# dualevse.net
KiCad netlist of a schematic drawn in EAGLE
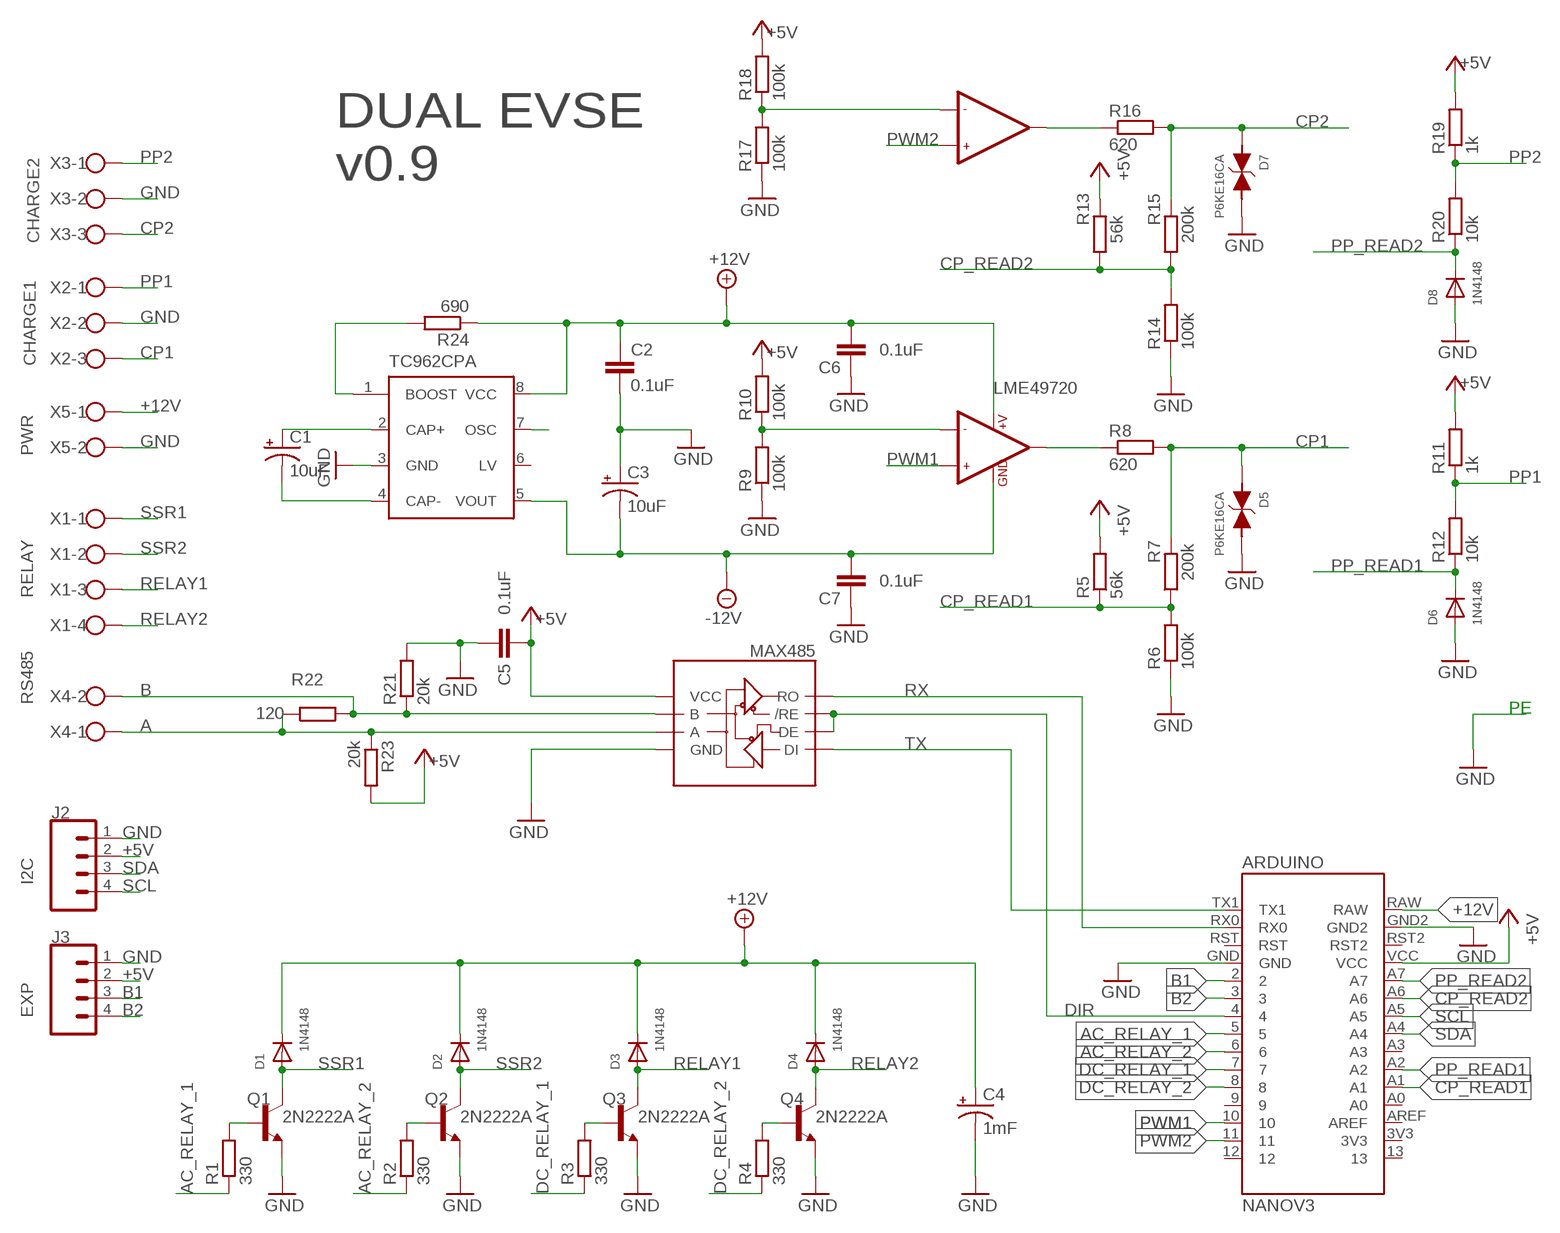
[diagram p0: schematic, sheet 1]

(export (version "E")
  (design (tool "Eeschema 10.0.6"))
  (components
    (comp (ref "ARDUINO")
      (value "NANOV3")
      (footprint "eagle-import:NANOV3")
      (libsource (lib "eagle-import") (part "NANOV3"))
    )
    (comp (ref "C1")
      (value "10uF")
      (footprint "eagle-import:CPOL-RADIAL-2.5MM-5MM")
      (libsource (lib "eagle-import") (part "10UF-POLAR-RADIAL-2.5MM-25V-20%"))
    )
    (comp (ref "C2")
      (value "0.1uF")
      (footprint "eagle-import:CAP-PTH-SMALL-KIT")
      (libsource (lib "eagle-import") (part "0.1UF-KIT-EZ-50V-20%"))
    )
    (comp (ref "C3")
      (value "10uF")
      (footprint "eagle-import:CPOL-RADIAL-2.5MM-5MM")
      (libsource (lib "eagle-import") (part "10UF-POLAR-RADIAL-2.5MM-25V-20%"))
    )
    (comp (ref "C4")
      (value "1mF")
      (footprint "eagle-import:CPOL-RADIAL-5MM-10MM")
      (libsource (lib "eagle-import") (part "1000UF-RADIAL-5MM-25V-20%"))
    )
    (comp (ref "C5")
      (value "0.1uF")
      (footprint "eagle-import:CAP-PTH-SMALL-KIT")
      (libsource (lib "eagle-import") (part "0.1UF-KIT-EZ-50V-20%"))
    )
    (comp (ref "C6")
      (value "0.1uF")
      (footprint "eagle-import:CAP-PTH-SMALL-KIT")
      (libsource (lib "eagle-import") (part "0.1UF-KIT-EZ-50V-20%"))
    )
    (comp (ref "C7")
      (value "0.1uF")
      (footprint "eagle-import:CAP-PTH-SMALL-KIT")
      (libsource (lib "eagle-import") (part "0.1UF-KIT-EZ-50V-20%"))
    )
    (comp (ref "D1")
      (value "1N4148")
      (footprint "eagle-import:DO-1N4148")
      (libsource (lib "eagle-import") (part "DIODEDO-1N4148"))
    )
    (comp (ref "D2")
      (value "1N4148")
      (footprint "eagle-import:DO-1N4148")
      (libsource (lib "eagle-import") (part "DIODEDO-1N4148"))
    )
    (comp (ref "D3")
      (value "1N4148")
      (footprint "eagle-import:DO-1N4148")
      (libsource (lib "eagle-import") (part "DIODEDO-1N4148"))
    )
    (comp (ref "D4")
      (value "1N4148")
      (footprint "eagle-import:DO-1N4148")
      (libsource (lib "eagle-import") (part "DIODEDO-1N4148"))
    )
    (comp (ref "D5")
      (value "P6KE16CA")
      (footprint "eagle-import:C4111-15")
      (libsource (lib "eagle-import") (part "TVSDO2"))
    )
    (comp (ref "D6")
      (value "1N4148")
      (footprint "eagle-import:DO-1N4148")
      (libsource (lib "eagle-import") (part "DIODEDO-1N4148"))
    )
    (comp (ref "D7")
      (value "P6KE16CA")
      (footprint "eagle-import:C4111-15")
      (libsource (lib "eagle-import") (part "TVSDO2"))
    )
    (comp (ref "D8")
      (value "1N4148")
      (footprint "eagle-import:DO-1N4148")
      (libsource (lib "eagle-import") (part "DIODEDO-1N4148"))
    )
    (comp (ref "J2")
      (value "I2C")
      (footprint "eagle-import:MOLEX-1X4")
      (libsource (lib "eagle-import") (part "CONN_04POLAR"))
    )
    (comp (ref "J3")
      (value "EXP")
      (footprint "eagle-import:MOLEX-1X4")
      (libsource (lib "eagle-import") (part "CONN_04POLAR"))
    )
    (comp (ref "LME49720")
      (value "LME49720")
      (footprint "eagle-import:TEXAS_DIL08")
      (libsource (lib "eagle-import") (part "LF353DIL08"))
    )
    (comp (ref "MAX485")
      (value "SPARKFUN-IC-COMMS_RS485")
      (footprint "eagle-import:TEXAS_DIL08")
      (libsource (lib "eagle-import") (part "SPARKFUN-IC-COMMS_RS485"))
    )
    (comp (ref "Q1")
      (value "2N2222A")
      (footprint "eagle-import:TO18")
      (libsource (lib "eagle-import") (part "2N2222A"))
    )
    (comp (ref "Q2")
      (value "2N2222A")
      (footprint "eagle-import:TO18")
      (libsource (lib "eagle-import") (part "2N2222A"))
    )
    (comp (ref "Q3")
      (value "2N2222A")
      (footprint "eagle-import:TO18")
      (libsource (lib "eagle-import") (part "2N2222A"))
    )
    (comp (ref "Q4")
      (value "2N2222A")
      (footprint "eagle-import:TO18")
      (libsource (lib "eagle-import") (part "2N2222A"))
    )
    (comp (ref "R1")
      (value "330")
      (footprint "eagle-import:0207_10")
      (libsource (lib "eagle-import") (part "R-EU_0207/10"))
    )
    (comp (ref "R2")
      (value "330")
      (footprint "eagle-import:0207_10")
      (libsource (lib "eagle-import") (part "R-EU_0207/10"))
    )
    (comp (ref "R3")
      (value "330")
      (footprint "eagle-import:0207_10")
      (libsource (lib "eagle-import") (part "R-EU_0207/10"))
    )
    (comp (ref "R4")
      (value "330")
      (footprint "eagle-import:0207_10")
      (libsource (lib "eagle-import") (part "R-EU_0207/10"))
    )
    (comp (ref "R5")
      (value "56k")
      (footprint "eagle-import:0207_10")
      (libsource (lib "eagle-import") (part "R-EU_0207/10"))
    )
    (comp (ref "R6")
      (value "100k")
      (footprint "eagle-import:0207_10")
      (libsource (lib "eagle-import") (part "R-EU_0207/10"))
    )
    (comp (ref "R7")
      (value "200k")
      (footprint "eagle-import:0207_10")
      (libsource (lib "eagle-import") (part "R-EU_0207/10"))
    )
    (comp (ref "R8")
      (value "620")
      (footprint "eagle-import:0207_10")
      (libsource (lib "eagle-import") (part "R-EU_0207/10"))
    )
    (comp (ref "R9")
      (value "100k")
      (footprint "eagle-import:0207_10")
      (libsource (lib "eagle-import") (part "R-EU_0207/10"))
    )
    (comp (ref "R10")
      (value "100k")
      (footprint "eagle-import:0207_10")
      (libsource (lib "eagle-import") (part "R-EU_0207/10"))
    )
    (comp (ref "R11")
      (value "1k")
      (footprint "eagle-import:0207_10")
      (libsource (lib "eagle-import") (part "R-EU_0207/10"))
    )
    (comp (ref "R12")
      (value "10k")
      (footprint "eagle-import:0207_10")
      (libsource (lib "eagle-import") (part "R-EU_0207/10"))
    )
    (comp (ref "R13")
      (value "56k")
      (footprint "eagle-import:0207_10")
      (libsource (lib "eagle-import") (part "R-EU_0207/10"))
    )
    (comp (ref "R14")
      (value "100k")
      (footprint "eagle-import:0207_10")
      (libsource (lib "eagle-import") (part "R-EU_0207/10"))
    )
    (comp (ref "R15")
      (value "200k")
      (footprint "eagle-import:0207_10")
      (libsource (lib "eagle-import") (part "R-EU_0207/10"))
    )
    (comp (ref "R16")
      (value "620")
      (footprint "eagle-import:0207_10")
      (libsource (lib "eagle-import") (part "R-EU_0207/10"))
    )
    (comp (ref "R17")
      (value "100k")
      (footprint "eagle-import:0207_10")
      (libsource (lib "eagle-import") (part "R-EU_0207/10"))
    )
    (comp (ref "R18")
      (value "100k")
      (footprint "eagle-import:0207_10")
      (libsource (lib "eagle-import") (part "R-EU_0207/10"))
    )
    (comp (ref "R19")
      (value "1k")
      (footprint "eagle-import:0207_10")
      (libsource (lib "eagle-import") (part "R-EU_0207/10"))
    )
    (comp (ref "R20")
      (value "10k")
      (footprint "eagle-import:0207_10")
      (libsource (lib "eagle-import") (part "R-EU_0207/10"))
    )
    (comp (ref "R21")
      (value "20k")
      (footprint "eagle-import:0207_10")
      (libsource (lib "eagle-import") (part "R-EU_0207/10"))
    )
    (comp (ref "R22")
      (value "120")
      (footprint "eagle-import:0207_10")
      (libsource (lib "eagle-import") (part "R-EU_0207/10"))
    )
    (comp (ref "R23")
      (value "20k")
      (footprint "eagle-import:0207_10")
      (libsource (lib "eagle-import") (part "R-EU_0207/10"))
    )
    (comp (ref "R24")
      (value "690")
      (footprint "eagle-import:0207_10")
      (libsource (lib "eagle-import") (part "R-EU_0207/10"))
    )
    (comp (ref "TC962CPA")
      (value "TEXAS_TL7660")
      (footprint "eagle-import:TEXAS_DIL08")
      (libsource (lib "eagle-import") (part "TEXAS_TL7660"))
    )
    (comp (ref "X1")
      (value "RELAY")
      (footprint "eagle-import:W237-4")
      (libsource (lib "eagle-import") (part "W237-4"))
    )
    (comp (ref "X2")
      (value "CHARGE1")
      (footprint "eagle-import:W237-103")
      (fields (field (name "MPN") "237-103"))
      (libsource (lib "eagle-import") (part "W237-103"))
    )
    (comp (ref "X3")
      (value "CHARGE2")
      (footprint "eagle-import:W237-103")
      (fields (field (name "MPN") "237-103"))
      (libsource (lib "eagle-import") (part "W237-103"))
    )
    (comp (ref "X4")
      (value "RS485")
      (footprint "eagle-import:W237-102")
      (fields (field (name "MPN") "237-102"))
      (libsource (lib "eagle-import") (part "W237-102"))
    )
    (comp (ref "X5")
      (value "PWR")
      (footprint "eagle-import:W237-102")
      (fields (field (name "MPN") "237-102"))
      (libsource (lib "eagle-import") (part "W237-102"))
    )
  )
  (nets
    (net (code "1") (name "+5V") (class "Default")
      (node (ref "ARDUINO") (pin "VCC") (pinfunction "VCC_VCC") (pintype "bidirectional"))
      (node (ref "C5") (pin "2") (pinfunction "2_2") (pintype "passive"))
      (node (ref "J2") (pin "2") (pinfunction "2_2") (pintype "passive"))
      (node (ref "J3") (pin "2") (pinfunction "2_2") (pintype "passive"))
      (node (ref "MAX485") (pin "8") (pinfunction "VCC_8") (pintype "bidirectional"))
      (node (ref "R10") (pin "2") (pinfunction "2_2") (pintype "passive"))
      (node (ref "R11") (pin "2") (pinfunction "2_2") (pintype "passive"))
      (node (ref "R13") (pin "2") (pinfunction "2_2") (pintype "passive"))
      (node (ref "R18") (pin "2") (pinfunction "2_2") (pintype "passive"))
      (node (ref "R19") (pin "2") (pinfunction "2_2") (pintype "passive"))
      (node (ref "R23") (pin "2") (pinfunction "2_2") (pintype "passive"))
      (node (ref "R5") (pin "2") (pinfunction "2_2") (pintype "passive"))
    )
    (net (code "2") (name "+12V") (class "Default")
      (node (ref "ARDUINO") (pin "RAW") (pinfunction "RAW_RAW") (pintype "bidirectional"))
      (node (ref "C2") (pin "1") (pinfunction "1_1") (pintype "passive"))
      (node (ref "C4") (pin "+") (pinfunction "+_+") (pintype "passive"))
      (node (ref "C6") (pin "1") (pinfunction "1_1") (pintype "passive"))
      (node (ref "D1") (pin "C") (pinfunction "C_C") (pintype "passive"))
      (node (ref "D2") (pin "C") (pinfunction "C_C") (pintype "passive"))
      (node (ref "D3") (pin "C") (pinfunction "C_C") (pintype "passive"))
      (node (ref "D4") (pin "C") (pinfunction "C_C") (pintype "passive"))
      (node (ref "LME49720") (pin "8") (pinfunction "+V_8") (pintype "power_in"))
      (node (ref "R24") (pin "1") (pinfunction "1_1") (pintype "passive"))
      (node (ref "TC962CPA") (pin "8") (pinfunction "VCC_8") (pintype "power_in"))
      (node (ref "X5") (pin "1") (pinfunction "KL_1") (pintype "passive"))
    )
    (net (code "3") (name "-12V") (class "Default")
      (node (ref "C3") (pin "2") (pinfunction "-_2") (pintype "passive"))
      (node (ref "C7") (pin "2") (pinfunction "2_2") (pintype "passive"))
      (node (ref "LME49720") (pin "4") (pinfunction "GND_4") (pintype "power_in"))
      (node (ref "TC962CPA") (pin "5") (pinfunction "VOUT_5") (pintype "passive"))
    )
    (net (code "4") (name "/A") (class "Default")
      (node (ref "MAX485") (pin "6") (pinfunction "A_6") (pintype "bidirectional"))
      (node (ref "R22") (pin "1") (pinfunction "1_1") (pintype "passive"))
      (node (ref "R23") (pin "1") (pinfunction "1_1") (pintype "passive"))
      (node (ref "X4") (pin "1") (pinfunction "KL_1") (pintype "passive"))
    )
    (net (code "5") (name "/B") (class "Default")
      (node (ref "MAX485") (pin "7") (pinfunction "B_7") (pintype "bidirectional"))
      (node (ref "R21") (pin "1") (pinfunction "1_1") (pintype "passive"))
      (node (ref "R22") (pin "2") (pinfunction "2_2") (pintype "passive"))
      (node (ref "X4") (pin "2") (pinfunction "KL_2") (pintype "passive"))
    )
    (net (code "6") (name "/CP1") (class "Default")
      (node (ref "D5") (pin "A") (pinfunction "1_A") (pintype "passive"))
      (node (ref "R7") (pin "2") (pinfunction "2_2") (pintype "passive"))
      (node (ref "R8") (pin "2") (pinfunction "2_2") (pintype "passive"))
      (node (ref "X2") (pin "3") (pinfunction "KL_3") (pintype "passive"))
    )
    (net (code "7") (name "/CP2") (class "Default")
      (node (ref "D7") (pin "A") (pinfunction "1_A") (pintype "passive"))
      (node (ref "R15") (pin "2") (pinfunction "2_2") (pintype "passive"))
      (node (ref "R16") (pin "2") (pinfunction "2_2") (pintype "passive"))
      (node (ref "X3") (pin "3") (pinfunction "KL_3") (pintype "passive"))
    )
    (net (code "8") (name "/DIR") (class "Default")
      (node (ref "ARDUINO") (pin "4") (pinfunction "4_4") (pintype "bidirectional"))
      (node (ref "MAX485") (pin "2") (pinfunction "/RE_2") (pintype "bidirectional"))
      (node (ref "MAX485") (pin "3") (pinfunction "DE_3") (pintype "bidirectional"))
    )
    (net (code "9") (name "/PP1") (class "Default")
      (node (ref "R11") (pin "1") (pinfunction "1_1") (pintype "passive"))
      (node (ref "R12") (pin "2") (pinfunction "2_2") (pintype "passive"))
      (node (ref "X2") (pin "1") (pinfunction "KL_1") (pintype "passive"))
    )
    (net (code "10") (name "/PP2") (class "Default")
      (node (ref "R19") (pin "1") (pinfunction "1_1") (pintype "passive"))
      (node (ref "R20") (pin "2") (pinfunction "2_2") (pintype "passive"))
      (node (ref "X3") (pin "1") (pinfunction "KL_1") (pintype "passive"))
    )
    (net (code "11") (name "/RELAY1") (class "Default")
      (node (ref "D3") (pin "A") (pinfunction "A_A") (pintype "passive"))
      (node (ref "Q3") (pin "3") (pinfunction "C_3") (pintype "passive"))
      (node (ref "X1") (pin "3") (pinfunction "KL_3") (pintype "passive"))
    )
    (net (code "12") (name "/RELAY2") (class "Default")
      (node (ref "D4") (pin "A") (pinfunction "A_A") (pintype "passive"))
      (node (ref "Q4") (pin "3") (pinfunction "C_3") (pintype "passive"))
      (node (ref "X1") (pin "4") (pinfunction "KL_4") (pintype "passive"))
    )
    (net (code "13") (name "/RX") (class "Default")
      (node (ref "ARDUINO") (pin "RX0") (pinfunction "RX0_RX0") (pintype "bidirectional"))
      (node (ref "MAX485") (pin "1") (pinfunction "RO_1") (pintype "bidirectional"))
    )
    (net (code "14") (name "/SSR1") (class "Default")
      (node (ref "D1") (pin "A") (pinfunction "A_A") (pintype "passive"))
      (node (ref "Q1") (pin "3") (pinfunction "C_3") (pintype "passive"))
      (node (ref "X1") (pin "1") (pinfunction "KL_1") (pintype "passive"))
    )
    (net (code "15") (name "/SSR2") (class "Default")
      (node (ref "D2") (pin "A") (pinfunction "A_A") (pintype "passive"))
      (node (ref "Q2") (pin "3") (pinfunction "C_3") (pintype "passive"))
      (node (ref "X1") (pin "2") (pinfunction "KL_2") (pintype "passive"))
    )
    (net (code "16") (name "/TX") (class "Default")
      (node (ref "ARDUINO") (pin "TX1") (pinfunction "TX1_TX1") (pintype "bidirectional"))
      (node (ref "MAX485") (pin "4") (pinfunction "DI_4") (pintype "bidirectional"))
    )
    (net (code "17") (name "AC_RELAY_1") (class "Default")
      (node (ref "ARDUINO") (pin "5") (pinfunction "5_5") (pintype "bidirectional"))
      (node (ref "R1") (pin "1") (pinfunction "1_1") (pintype "passive"))
    )
    (net (code "18") (name "AC_RELAY_2") (class "Default")
      (node (ref "ARDUINO") (pin "6") (pinfunction "6_6") (pintype "bidirectional"))
      (node (ref "R2") (pin "1") (pinfunction "1_1") (pintype "passive"))
    )
    (net (code "19") (name "B1") (class "Default")
      (node (ref "ARDUINO") (pin "2") (pinfunction "2_2") (pintype "bidirectional"))
      (node (ref "J3") (pin "3") (pinfunction "3_3") (pintype "passive"))
    )
    (net (code "20") (name "B2") (class "Default")
      (node (ref "ARDUINO") (pin "3") (pinfunction "3_3") (pintype "bidirectional"))
      (node (ref "J3") (pin "4") (pinfunction "4_4") (pintype "passive"))
    )
    (net (code "21") (name "CP_READ1") (class "Default")
      (node (ref "ARDUINO") (pin "A1") (pinfunction "A1_A1") (pintype "bidirectional"))
      (node (ref "R5") (pin "1") (pinfunction "1_1") (pintype "passive"))
      (node (ref "R6") (pin "2") (pinfunction "2_2") (pintype "passive"))
      (node (ref "R7") (pin "1") (pinfunction "1_1") (pintype "passive"))
    )
    (net (code "22") (name "CP_READ2") (class "Default")
      (node (ref "ARDUINO") (pin "A6") (pinfunction "A6_A6") (pintype "bidirectional"))
      (node (ref "R13") (pin "1") (pinfunction "1_1") (pintype "passive"))
      (node (ref "R14") (pin "2") (pinfunction "2_2") (pintype "passive"))
      (node (ref "R15") (pin "1") (pinfunction "1_1") (pintype "passive"))
    )
    (net (code "23") (name "DC_RELAY_1") (class "Default")
      (node (ref "ARDUINO") (pin "7") (pinfunction "7_7") (pintype "bidirectional"))
      (node (ref "R3") (pin "1") (pinfunction "1_1") (pintype "passive"))
    )
    (net (code "24") (name "DC_RELAY_2") (class "Default")
      (node (ref "ARDUINO") (pin "8") (pinfunction "8_8") (pintype "bidirectional"))
      (node (ref "R4") (pin "1") (pinfunction "1_1") (pintype "passive"))
    )
    (net (code "25") (name "GND") (class "Default")
      (node (ref "ARDUINO") (pin "GND") (pinfunction "GND_GND") (pintype "bidirectional"))
      (node (ref "ARDUINO") (pin "GND2") (pinfunction "GND2_GND2") (pintype "bidirectional"))
      (node (ref "C2") (pin "2") (pinfunction "2_2") (pintype "passive"))
      (node (ref "C3") (pin "1") (pinfunction "+_1") (pintype "passive"))
      (node (ref "C4") (pin "-") (pinfunction "-_-") (pintype "passive"))
      (node (ref "C5") (pin "1") (pinfunction "1_1") (pintype "passive"))
      (node (ref "C6") (pin "2") (pinfunction "2_2") (pintype "passive"))
      (node (ref "C7") (pin "1") (pinfunction "1_1") (pintype "passive"))
      (node (ref "D5") (pin "C") (pinfunction "2_C") (pintype "passive"))
      (node (ref "D6") (pin "A") (pinfunction "A_A") (pintype "passive"))
      (node (ref "D7") (pin "C") (pinfunction "2_C") (pintype "passive"))
      (node (ref "D8") (pin "A") (pinfunction "A_A") (pintype "passive"))
      (node (ref "J2") (pin "1") (pinfunction "1_1") (pintype "passive"))
      (node (ref "J3") (pin "1") (pinfunction "1_1") (pintype "passive"))
      (node (ref "MAX485") (pin "5") (pinfunction "GND_5") (pintype "bidirectional"))
      (node (ref "Q1") (pin "1") (pinfunction "E_1") (pintype "passive"))
      (node (ref "Q2") (pin "1") (pinfunction "E_1") (pintype "passive"))
      (node (ref "Q3") (pin "1") (pinfunction "E_1") (pintype "passive"))
      (node (ref "Q4") (pin "1") (pinfunction "E_1") (pintype "passive"))
      (node (ref "R14") (pin "1") (pinfunction "1_1") (pintype "passive"))
      (node (ref "R17") (pin "1") (pinfunction "1_1") (pintype "passive"))
      (node (ref "R21") (pin "2") (pinfunction "2_2") (pintype "passive"))
      (node (ref "R6") (pin "1") (pinfunction "1_1") (pintype "passive"))
      (node (ref "R9") (pin "1") (pinfunction "1_1") (pintype "passive"))
      (node (ref "TC962CPA") (pin "3") (pinfunction "GND_3") (pintype "power_in"))
      (node (ref "X2") (pin "2") (pinfunction "KL_2") (pintype "passive"))
      (node (ref "X3") (pin "2") (pinfunction "KL_2") (pintype "passive"))
      (node (ref "X5") (pin "2") (pinfunction "KL_2") (pintype "passive"))
    )
    (net (code "26") (name "Net-(C1-+)") (class "Default")
      (node (ref "C1") (pin "1") (pinfunction "+_1") (pintype "passive"))
      (node (ref "TC962CPA") (pin "2") (pinfunction "CAP+_2") (pintype "passive"))
    )
    (net (code "27") (name "Net-(C1--)") (class "Default")
      (node (ref "C1") (pin "2") (pinfunction "-_2") (pintype "passive"))
      (node (ref "TC962CPA") (pin "4") (pinfunction "CAP-_4") (pintype "passive"))
    )
    (net (code "28") (name "Net-(LME49720A--IN1)") (class "Default")
      (node (ref "LME49720") (pin "2") (pinfunction "-IN1_2") (pintype "input"))
      (node (ref "R10") (pin "1") (pinfunction "1_1") (pintype "passive"))
      (node (ref "R9") (pin "2") (pinfunction "2_2") (pintype "passive"))
    )
    (net (code "29") (name "Net-(LME49720A-OUT1)") (class "Default")
      (node (ref "LME49720") (pin "1") (pinfunction "OUT1_1") (pintype "output"))
      (node (ref "R8") (pin "1") (pinfunction "1_1") (pintype "passive"))
    )
    (net (code "30") (name "Net-(LME49720B--IN2)") (class "Default")
      (node (ref "LME49720") (pin "6") (pinfunction "-IN2_6") (pintype "input"))
      (node (ref "R17") (pin "2") (pinfunction "2_2") (pintype "passive"))
      (node (ref "R18") (pin "1") (pinfunction "1_1") (pintype "passive"))
    )
    (net (code "31") (name "Net-(LME49720B-OUT2)") (class "Default")
      (node (ref "LME49720") (pin "7") (pinfunction "OUT2_7") (pintype "output"))
      (node (ref "R16") (pin "1") (pinfunction "1_1") (pintype "passive"))
    )
    (net (code "32") (name "Net-(Q1-B)") (class "Default")
      (node (ref "Q1") (pin "2") (pinfunction "B_2") (pintype "passive"))
      (node (ref "R1") (pin "2") (pinfunction "2_2") (pintype "passive"))
    )
    (net (code "33") (name "Net-(Q2-B)") (class "Default")
      (node (ref "Q2") (pin "2") (pinfunction "B_2") (pintype "passive"))
      (node (ref "R2") (pin "2") (pinfunction "2_2") (pintype "passive"))
    )
    (net (code "34") (name "Net-(Q3-B)") (class "Default")
      (node (ref "Q3") (pin "2") (pinfunction "B_2") (pintype "passive"))
      (node (ref "R3") (pin "2") (pinfunction "2_2") (pintype "passive"))
    )
    (net (code "35") (name "Net-(Q4-B)") (class "Default")
      (node (ref "Q4") (pin "2") (pinfunction "B_2") (pintype "passive"))
      (node (ref "R4") (pin "2") (pinfunction "2_2") (pintype "passive"))
    )
    (net (code "36") (name "Net-(TC962CPA-BOOST)") (class "Default")
      (node (ref "R24") (pin "2") (pinfunction "2_2") (pintype "passive"))
      (node (ref "TC962CPA") (pin "1") (pinfunction "BOOST_1") (pintype "bidirectional"))
    )
    (net (code "37") (name "PP_READ1") (class "Default")
      (node (ref "ARDUINO") (pin "A2") (pinfunction "A2_A2") (pintype "bidirectional"))
      (node (ref "D6") (pin "C") (pinfunction "C_C") (pintype "passive"))
      (node (ref "R12") (pin "1") (pinfunction "1_1") (pintype "passive"))
    )
    (net (code "38") (name "PP_READ2") (class "Default")
      (node (ref "ARDUINO") (pin "A7") (pinfunction "A7_A7") (pintype "bidirectional"))
      (node (ref "D8") (pin "C") (pinfunction "C_C") (pintype "passive"))
      (node (ref "R20") (pin "1") (pinfunction "1_1") (pintype "passive"))
    )
    (net (code "39") (name "PWM1") (class "Default")
      (node (ref "ARDUINO") (pin "10") (pinfunction "10_10") (pintype "bidirectional"))
      (node (ref "LME49720") (pin "3") (pinfunction "+IN1_3") (pintype "input"))
    )
    (net (code "40") (name "PWM2") (class "Default")
      (node (ref "ARDUINO") (pin "11") (pinfunction "11_11") (pintype "bidirectional"))
      (node (ref "LME49720") (pin "5") (pinfunction "+IN2_5") (pintype "input"))
    )
    (net (code "41") (name "SCL") (class "Default")
      (node (ref "ARDUINO") (pin "A5") (pinfunction "A5_A5") (pintype "bidirectional"))
      (node (ref "J2") (pin "4") (pinfunction "4_4") (pintype "passive"))
    )
    (net (code "42") (name "SDA") (class "Default")
      (node (ref "ARDUINO") (pin "A4") (pinfunction "A4_A4") (pintype "bidirectional"))
      (node (ref "J2") (pin "3") (pinfunction "3_3") (pintype "passive"))
    )
    (net (code "43") (name "unconnected-(ARDUINO-Pad3V3)") (class "Default")
      (node (ref "ARDUINO") (pin "3V3") (pinfunction "3V3_3V3") (pintype "bidirectional"))
    )
    (net (code "44") (name "unconnected-(ARDUINO-Pad9)") (class "Default")
      (node (ref "ARDUINO") (pin "9") (pinfunction "9_9") (pintype "bidirectional"))
    )
    (net (code "45") (name "unconnected-(ARDUINO-Pad12)") (class "Default")
      (node (ref "ARDUINO") (pin "12") (pinfunction "12_12") (pintype "bidirectional"))
    )
    (net (code "46") (name "unconnected-(ARDUINO-Pad13)") (class "Default")
      (node (ref "ARDUINO") (pin "13") (pinfunction "13_13") (pintype "bidirectional"))
    )
    (net (code "47") (name "unconnected-(ARDUINO-PadA0)") (class "Default")
      (node (ref "ARDUINO") (pin "A0") (pinfunction "A0_A0") (pintype "bidirectional"))
    )
    (net (code "48") (name "unconnected-(ARDUINO-PadA3)") (class "Default")
      (node (ref "ARDUINO") (pin "A3") (pinfunction "A3_A3") (pintype "bidirectional"))
    )
    (net (code "49") (name "unconnected-(ARDUINO-PadAREF)") (class "Default")
      (node (ref "ARDUINO") (pin "AREF") (pinfunction "AREF_AREF") (pintype "bidirectional"))
    )
    (net (code "50") (name "unconnected-(ARDUINO-PadRST)") (class "Default")
      (node (ref "ARDUINO") (pin "RST") (pinfunction "RST_RST") (pintype "bidirectional"))
    )
    (net (code "51") (name "unconnected-(ARDUINO-PadRST2)") (class "Default")
      (node (ref "ARDUINO") (pin "RST2") (pinfunction "RST2_RST2") (pintype "bidirectional"))
    )
    (net (code "52") (name "unconnected-(TC962CPA-LV-Pad6)") (class "Default")
      (node (ref "TC962CPA") (pin "6") (pinfunction "LV_6") (pintype "passive"))
    )
    (net (code "53") (name "unconnected-(TC962CPA-OSC-Pad7)") (class "Default")
      (node (ref "TC962CPA") (pin "7") (pinfunction "OSC_7") (pintype "input"))
    )
  )
)
